# Head.net
KiCad netlist of a schematic drawn in Altium Designer
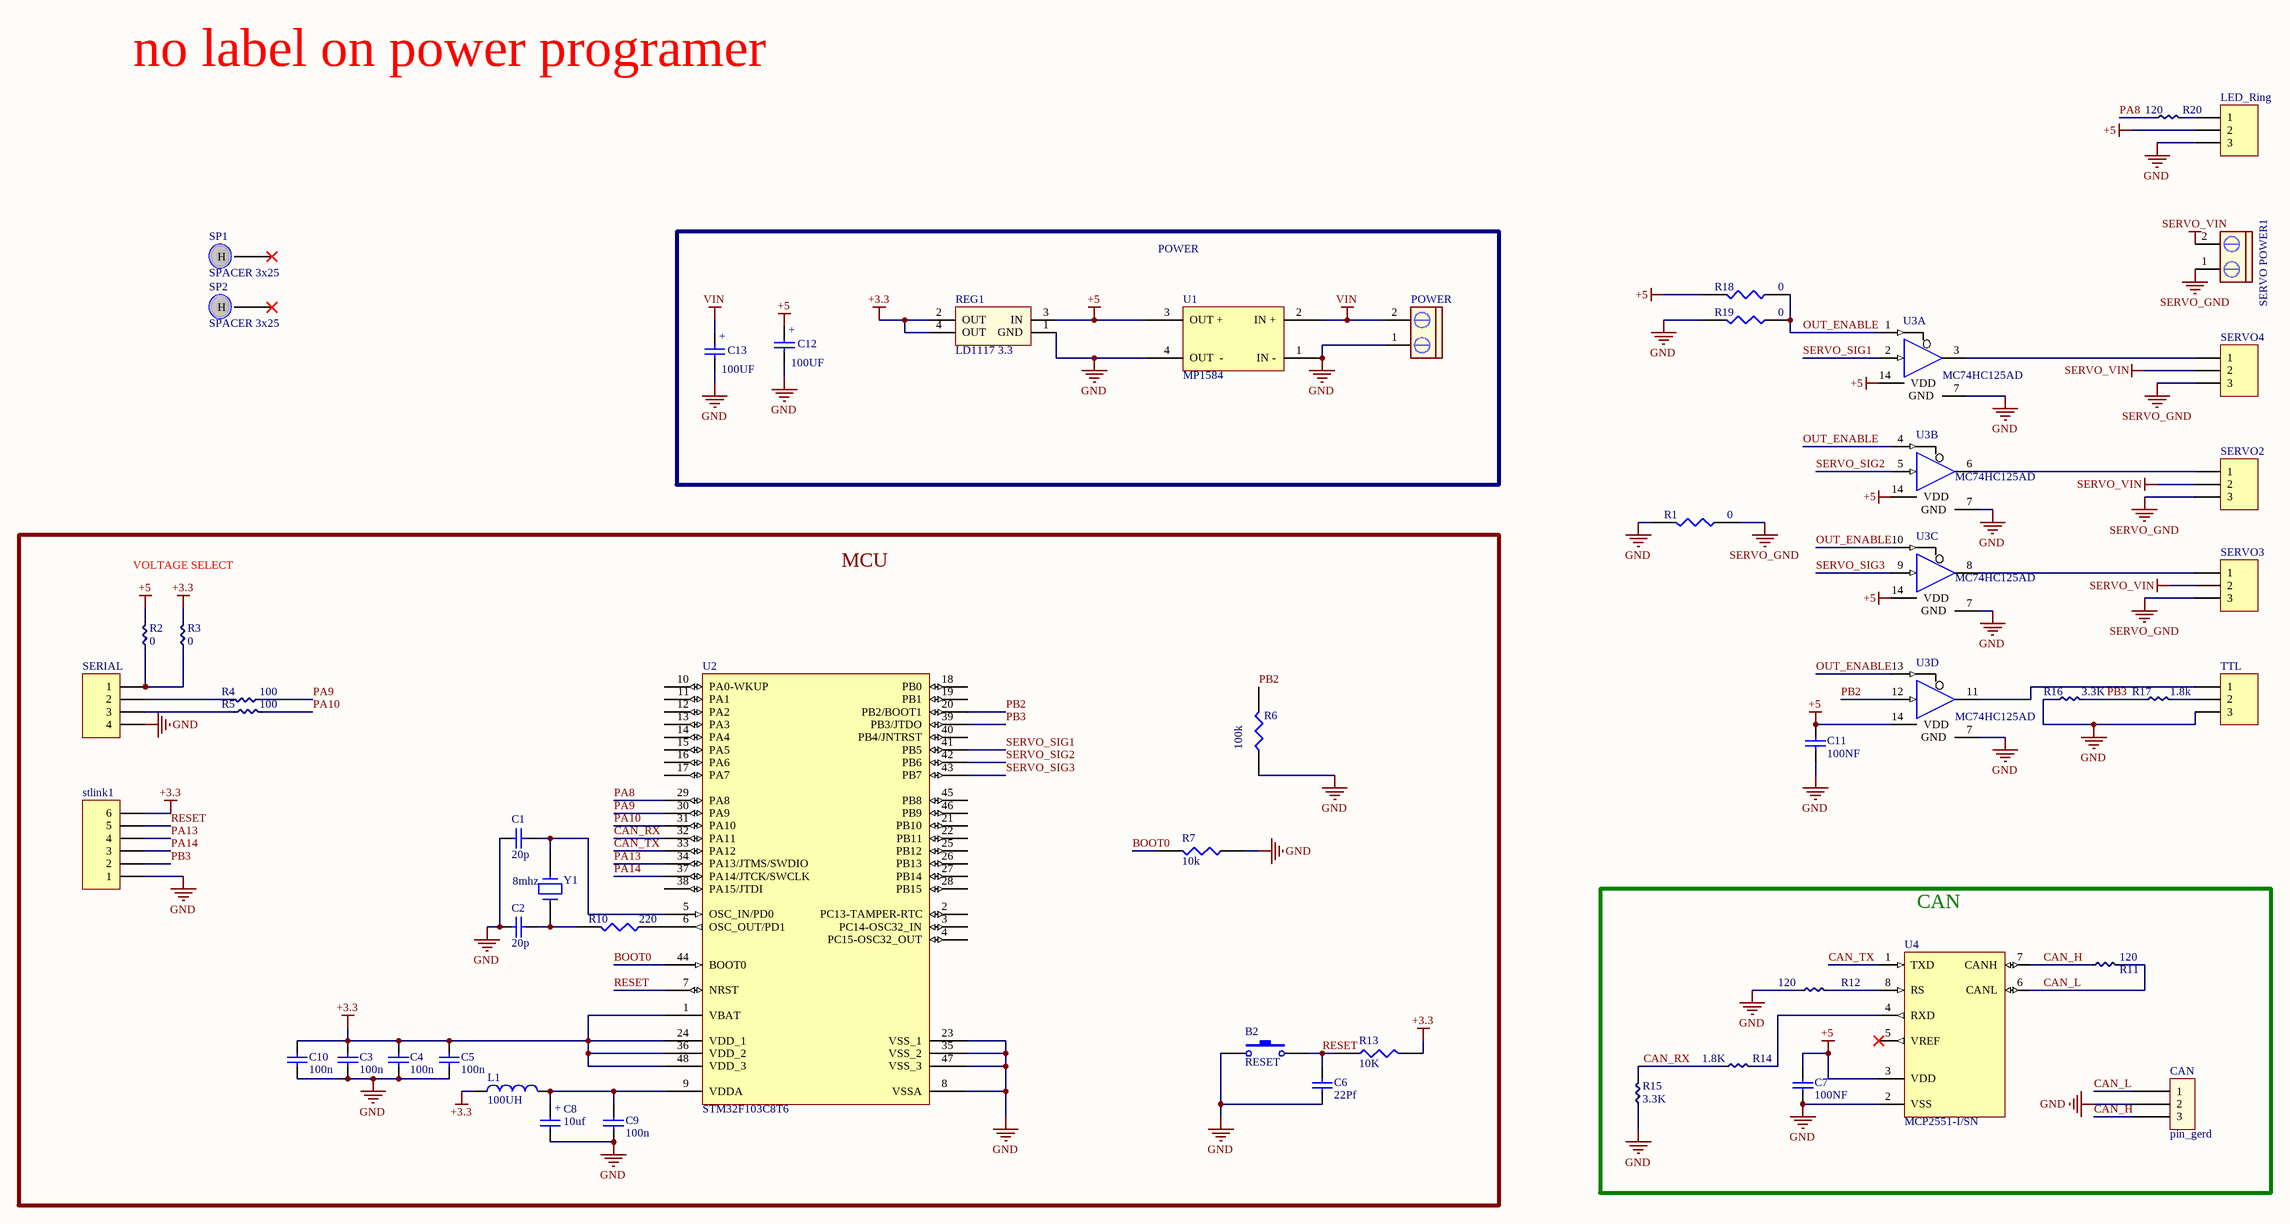
[diagram p0: Head.SchDoc]

(export (version "E")
  (design (tool "Eeschema 10.0.6"))
  (components
    (comp (ref "B2")
      (value "RESET")
      (footprint "SMD PUSH BUTTON")
      (libsource (lib "AMINLIB") (part "SMD_PUSH_BUTTON"))
    )
    (comp (ref "C1") (value "20p") (footprint "MY_CAP_SMD_0805") (libsource (lib "AMINLIB") (part "CAP SMD")))
    (comp (ref "C2") (value "20p") (footprint "MY_CAP_SMD_0805") (libsource (lib "AMINLIB") (part "CAP SMD")))
    (comp (ref "C3")
      (value "100n")
      (footprint "MY_CAP_SMD_0805")
      (libsource (lib "AMINLIB") (part "CAP SMD"))
    )
    (comp (ref "C4")
      (value "100n")
      (footprint "MY_CAP_SMD_0805")
      (libsource (lib "AMINLIB") (part "CAP SMD"))
    )
    (comp (ref "C5")
      (value "100n")
      (footprint "MY_CAP_SMD_0805")
      (libsource (lib "AMINLIB") (part "CAP SMD"))
    )
    (comp (ref "C6")
      (value "22Pf")
      (footprint "MY_CAP_SMD_0805")
      (libsource (lib "AMINLIB") (part "CAP SMD"))
    )
    (comp (ref "C7")
      (value "100NF")
      (footprint "MY_CAP_SMD_0805")
      (description "2.0 mm × 1.25 mm")
      (libsource (lib "AMINLIB") (part "CAP SMD_0805"))
    )
    (comp (ref "C8")
      (value "10uf")
      (footprint "MY_cap_smd10uf")
      (libsource (lib "AMINLIB") (part "cap_smd_10u"))
    )
    (comp (ref "C9")
      (value "100n")
      (footprint "MY_CAP_SMD_0805")
      (libsource (lib "AMINLIB") (part "CAP SMD"))
    )
    (comp (ref "C10")
      (value "100n")
      (footprint "MY_CAP_SMD_0805")
      (libsource (lib "AMINLIB") (part "CAP SMD"))
    )
    (comp (ref "C11")
      (value "100NF")
      (footprint "MY_CAP_SMD_0805")
      (description "2.0 mm × 1.25 mm")
      (libsource (lib "AMINLIB") (part "CAP SMD_0805"))
    )
    (comp (ref "C12")
      (value "100UF")
      (footprint "MY_CAP_POL 5MM")
      (description "CAP-3300Uf")
      (libsource (lib "AMINLIB") (part "Cap Pol_5mm"))
    )
    (comp (ref "C13")
      (value "100UF")
      (footprint "MY_CAP_POL 5MM")
      (description "CAP-3300Uf")
      (libsource (lib "AMINLIB") (part "Cap Pol_5mm"))
    )
    (comp (ref "CAN")
      (value "pin_gerd")
      (footprint "MY_PINGERD3")
      (description "3pin")
      (libsource (lib "AMINLIB") (part "pin_gerd"))
    )
    (comp (ref "L1")
      (value "100UH")
      (footprint "MY_SMD_INDUCTOR")
      (libsource (lib "AMINLIB") (part "INDUCTOR SMD"))
    )
    (comp (ref "LED_Ring")
      (value "Header 3")
      (footprint "My_1X03")
      (description "Header, 3-Pin")
      (fields (field (name "PUBLISHER") "Altium Limited"))
      (libsource (lib "AMINLIB") (part "Header 3"))
    )
    (comp (ref "POWER")
      (value "CON2 pin blue")
      (footprint "My_CN2")
      (description "Connector blue screw")
      (libsource (lib "AMINLIB") (part "CON2 pin blue"))
    )
    (comp (ref "R1") (value "0") (footprint "MY_RES_SMD_0805") (libsource (lib "AMINLIB") (part "RES SMD")))
    (comp (ref "R2")
      (value "0")
      (footprint "MY_RES_SMD_0805")
      (libsource (lib "AMINLIB") (part "RES SMD 0805"))
    )
    (comp (ref "R3")
      (value "0")
      (footprint "MY_RES_SMD_0805")
      (libsource (lib "AMINLIB") (part "RES SMD 0805"))
    )
    (comp (ref "R4")
      (value "100")
      (footprint "MY_RES_SMD_0805")
      (libsource (lib "AMINLIB") (part "RES SMD 0805"))
    )
    (comp (ref "R5")
      (value "100")
      (footprint "MY_RES_SMD_0805")
      (libsource (lib "AMINLIB") (part "RES SMD 0805"))
    )
    (comp (ref "R6")
      (value "100k")
      (footprint "MY_RES_SMD_0805")
      (libsource (lib "AMINLIB") (part "RES SMD"))
    )
    (comp (ref "R7") (value "10k") (footprint "MY_RES_SMD_0805") (libsource (lib "AMINLIB") (part "RES SMD")))
    (comp (ref "R10")
      (value "220")
      (footprint "MY_RES_SMD_0805")
      (libsource (lib "AMINLIB") (part "RES SMD"))
    )
    (comp (ref "R11")
      (value "120")
      (footprint "MY_RES_SMD_0805")
      (libsource (lib "AMINLIB") (part "RES SMD 0805"))
    )
    (comp (ref "R12")
      (value "120")
      (footprint "MY_RES_SMD_0805")
      (libsource (lib "AMINLIB") (part "RES SMD 0805"))
    )
    (comp (ref "R13")
      (value "10K")
      (footprint "MY_RES_SMD_0805")
      (libsource (lib "AMINLIB") (part "RES SMD"))
    )
    (comp (ref "R14")
      (value "1.8K")
      (footprint "MY_RES_SMD_0805")
      (libsource (lib "AMINLIB") (part "RES SMD 0805"))
    )
    (comp (ref "R15")
      (value "3.3K")
      (footprint "MY_RES_SMD_0805")
      (libsource (lib "AMINLIB") (part "RES SMD 0805"))
    )
    (comp (ref "R16")
      (value "3.3K")
      (footprint "MY_RES_SMD_0805")
      (libsource (lib "AMINLIB") (part "RES SMD 0805"))
    )
    (comp (ref "R17")
      (value "1.8k")
      (footprint "MY_RES_SMD_0805")
      (libsource (lib "AMINLIB") (part "RES SMD 0805"))
    )
    (comp (ref "R18") (value "0") (footprint "MY_RES_SMD_0805") (libsource (lib "AMINLIB") (part "RES SMD")))
    (comp (ref "R19") (value "0") (footprint "MY_RES_SMD_0805") (libsource (lib "AMINLIB") (part "RES SMD")))
    (comp (ref "R20")
      (value "120")
      (footprint "MY_RES_SMD_0805")
      (libsource (lib "AMINLIB") (part "RES SMD 0805"))
    )
    (comp (ref "REG1")
      (value "LD1117 3.3")
      (footprint "MY_LD1117-3.3")
      (libsource (lib "AMINLIB") (part "LD1117 3.3"))
    )
    (comp (ref "SERIAL")
      (value "Header 4")
      (footprint "My_1X04")
      (description "Header, 4-Pin")
      (fields (field (name "PUBLISHER") "Altium Limited"))
      (libsource (lib "AMINLIB") (part "Header 4"))
    )
    (comp (ref "SERVO POWER1")
      (value "CON2 pin blue")
      (footprint "My_CN2")
      (description "Connector blue screw")
      (libsource (lib "AMINLIB") (part "CON2 pin blue"))
    )
    (comp (ref "SERVO2")
      (value "Header 3")
      (footprint "My_1X03")
      (description "Header, 3-Pin")
      (fields (field (name "PUBLISHER") "Altium Limited"))
      (libsource (lib "AMINLIB") (part "Header 3"))
    )
    (comp (ref "SERVO3")
      (value "Header 3")
      (footprint "My_1X03")
      (description "Header, 3-Pin")
      (fields (field (name "PUBLISHER") "Altium Limited"))
      (libsource (lib "AMINLIB") (part "Header 3"))
    )
    (comp (ref "SERVO4")
      (value "Header 3")
      (footprint "My_1X03")
      (description "Header, 3-Pin")
      (fields (field (name "PUBLISHER") "Altium Limited"))
      (libsource (lib "AMINLIB") (part "Header 3"))
    )
    (comp (ref "SP1")
      (value "SPACER 3x25")
      (footprint "MY_SPACER 3X25MM")
      (description "SACER 3MM")
      (libsource (lib "AMINLIB") (part "SPACER 3x25"))
    )
    (comp (ref "SP2")
      (value "SPACER 3x25")
      (footprint "MY_SPACER 3X25MM")
      (description "SACER 3MM")
      (libsource (lib "AMINLIB") (part "SPACER 3x25"))
    )
    (comp (ref "stlink1")
      (value "Header 6")
      (footprint "My_1X06")
      (description "Header, 6-Pin")
      (fields (field (name "PUBLISHER") "Altium Limited"))
      (libsource (lib "AMINLIB") (part "Header 6"))
    )
    (comp (ref "TTL")
      (value "Header 3")
      (footprint "My_1X03")
      (description "Header, 3-Pin")
      (fields (field (name "PUBLISHER") "Altium Limited"))
      (libsource (lib "AMINLIB") (part "Header 3"))
    )
    (comp (ref "U1")
      (value "MP1584")
      (footprint "mp1584")
      (description "SWITCHING REGULATOR MODULE")
      (libsource (lib "AMINLIB") (part "MP1584"))
    )
    (comp (ref "U2")
      (value "STM32F103C8T6")
      (footprint "LQFP48_N")
      (description "STM32 ARM-based 32-bit MCU with 64 Kbytes Flash, 48-pin LQFP, Industrial Temperature")
      (fields (field (name "PUBLISHER") "Altium Limited"))
      (libsource (lib "ST Microcontroller 32-Bit STM32") (part "STM32F103C8T6"))
    )
    (comp (ref "U3")
      (value "MC74HC125AD")
      (footprint "751A-02_N")
      (description "Quad 3-State Non-Inverting Buffer")
      (fields (field (name "PUBLISHER") "Altium Limited"))
      (libsource (lib "Motorola Logic Buffer Line Driver") (part "MC74HC125AD"))
    )
    (comp (ref "U4")
      (value "MCP2551-I/SN")
      (footprint "SOIC-SN8_N")
      (description "High-Speed CAN Transceiver, 8-Pin SOIC, Industrial Temperature")
      (fields (field (name "PUBLISHER") "Altium Limited"))
      (libsource (lib "Microchip Interface") (part "MCP2551-I/SN"))
    )
    (comp (ref "Y1")
      (value "8mhz")
      (footprint "My_Crystal - SMD")
      (description "Crystal")
      (libsource (lib "AMINLIB") (part "CRYSTAL"))
    )
  )
  (nets
    (net (code "1") (name "+3.3") (class "Default")
      (node (ref "C10") (pin "2") (pinfunction "2_2") (pintype "passive"))
      (node (ref "C3") (pin "2") (pinfunction "2_2") (pintype "passive"))
      (node (ref "C4") (pin "2") (pinfunction "2_2") (pintype "passive"))
      (node (ref "C5") (pin "2") (pinfunction "2_2") (pintype "passive"))
      (node (ref "L1") (pin "1") (pinfunction "1_1") (pintype "passive"))
      (node (ref "R13") (pin "2") (pinfunction "2_2") (pintype "passive"))
      (node (ref "R3") (pin "2") (pinfunction "2_2") (pintype "passive"))
      (node (ref "REG1") (pin "2") (pinfunction "OUT_2") (pintype "power_in"))
      (node (ref "REG1") (pin "4") (pinfunction "OUT_4") (pintype "power_in"))
      (node (ref "U2") (pin "1") (pinfunction "VBAT_1") (pintype "power_in"))
      (node (ref "U2") (pin "24") (pinfunction "VDD_1_24") (pintype "power_in"))
      (node (ref "U2") (pin "36") (pinfunction "VDD_2_36") (pintype "power_in"))
      (node (ref "U2") (pin "48") (pinfunction "VDD_3_48") (pintype "power_in"))
      (node (ref "stlink1") (pin "6") (pinfunction "6_6") (pintype "passive"))
    )
    (net (code "2") (name "+5") (class "Default")
      (node (ref "C11") (pin "2") (pinfunction "2_2") (pintype "passive"))
      (node (ref "C12") (pin "+") (pinfunction "+_+") (pintype "passive"))
      (node (ref "C7") (pin "2") (pinfunction "2_2") (pintype "passive"))
      (node (ref "LED_Ring") (pin "2") (pinfunction "2_2") (pintype "passive"))
      (node (ref "R18") (pin "2") (pinfunction "2_2") (pintype "passive"))
      (node (ref "R2") (pin "2") (pinfunction "2_2") (pintype "passive"))
      (node (ref "REG1") (pin "3") (pinfunction "IN_3") (pintype "power_in"))
      (node (ref "U1") (pin "3") (pinfunction "OUT_+_3") (pintype "passive"))
      (node (ref "U3") (pin "14") (pinfunction "VDD_14") (pintype "power_in"))
      (node (ref "U4") (pin "3") (pinfunction "VDD_3") (pintype "power_in"))
    )
    (net (code "3") (name "/BOOT0") (class "Default")
      (node (ref "R7") (pin "2") (pinfunction "2_2") (pintype "passive"))
      (node (ref "U2") (pin "44") (pinfunction "BOOT0_44") (pintype "input"))
    )
    (net (code "4") (name "/CAN_H") (class "Default")
      (node (ref "CAN") (pin "3") (pinfunction "3_3") (pintype "passive"))
      (node (ref "R11") (pin "1") (pinfunction "1_1") (pintype "passive"))
      (node (ref "U4") (pin "7") (pinfunction "CANH_7") (pintype "bidirectional"))
    )
    (net (code "5") (name "/CAN_L") (class "Default")
      (node (ref "CAN") (pin "1") (pinfunction "1_1") (pintype "passive"))
      (node (ref "R11") (pin "2") (pinfunction "2_2") (pintype "passive"))
      (node (ref "U4") (pin "6") (pinfunction "CANL_6") (pintype "bidirectional"))
    )
    (net (code "6") (name "/CAN_RX") (class "Default")
      (node (ref "R14") (pin "1") (pinfunction "1_1") (pintype "passive"))
      (node (ref "R15") (pin "2") (pinfunction "2_2") (pintype "passive"))
      (node (ref "U2") (pin "32") (pinfunction "PA11_32") (pintype "bidirectional"))
    )
    (net (code "7") (name "/CAN_TX") (class "Default")
      (node (ref "U2") (pin "33") (pinfunction "PA12_33") (pintype "bidirectional"))
      (node (ref "U4") (pin "1") (pinfunction "TXD_1") (pintype "input"))
    )
    (net (code "8") (name "/OUT_ENABLE") (class "Default")
      (node (ref "R18") (pin "1") (pinfunction "1_1") (pintype "passive"))
      (node (ref "R19") (pin "1") (pinfunction "1_1") (pintype "passive"))
      (node (ref "U3") (pin "1") (pinfunction "~{OE}_1") (pintype "input"))
      (node (ref "U3") (pin "10") (pinfunction "~{OE}_10") (pintype "input"))
      (node (ref "U3") (pin "13") (pinfunction "~{OE}_13") (pintype "input"))
      (node (ref "U3") (pin "4") (pinfunction "~{OE}_4") (pintype "input"))
    )
    (net (code "9") (name "/PA8") (class "Default")
      (node (ref "R20") (pin "1") (pinfunction "1_1") (pintype "passive"))
      (node (ref "U2") (pin "29") (pinfunction "PA8_29") (pintype "bidirectional"))
    )
    (net (code "10") (name "/PA9") (class "Default")
      (node (ref "R4") (pin "1") (pinfunction "1_1") (pintype "passive"))
      (node (ref "U2") (pin "30") (pinfunction "PA9_30") (pintype "bidirectional"))
    )
    (net (code "11") (name "/PA10") (class "Default")
      (node (ref "R5") (pin "2") (pinfunction "2_2") (pintype "passive"))
      (node (ref "U2") (pin "31") (pinfunction "PA10_31") (pintype "bidirectional"))
    )
    (net (code "12") (name "/PA13") (class "Default")
      (node (ref "U2") (pin "34") (pinfunction "PA13/JTMS/SWDIO_34") (pintype "bidirectional"))
      (node (ref "stlink1") (pin "4") (pinfunction "4_4") (pintype "passive"))
    )
    (net (code "13") (name "/PA14") (class "Default")
      (node (ref "U2") (pin "37") (pinfunction "PA14/JTCK/SWCLK_37") (pintype "bidirectional"))
      (node (ref "stlink1") (pin "3") (pinfunction "3_3") (pintype "passive"))
    )
    (net (code "14") (name "/PB2") (class "Default")
      (node (ref "R6") (pin "2") (pinfunction "2_2") (pintype "passive"))
      (node (ref "U2") (pin "20") (pinfunction "PB2/BOOT1_20") (pintype "bidirectional"))
      (node (ref "U3") (pin "12") (pinfunction "A_12") (pintype "input"))
    )
    (net (code "15") (name "/PB3") (class "Default")
      (node (ref "R16") (pin "2") (pinfunction "2_2") (pintype "passive"))
      (node (ref "R17") (pin "1") (pinfunction "1_1") (pintype "passive"))
      (node (ref "U2") (pin "39") (pinfunction "PB3/JTDO_39") (pintype "bidirectional"))
      (node (ref "stlink1") (pin "2") (pinfunction "2_2") (pintype "passive"))
    )
    (net (code "16") (name "/RESET") (class "Default")
      (node (ref "B2") (pin "2") (pinfunction "2_2") (pintype "passive"))
      (node (ref "C6") (pin "2") (pinfunction "2_2") (pintype "passive"))
      (node (ref "R13") (pin "1") (pinfunction "1_1") (pintype "passive"))
      (node (ref "U2") (pin "7") (pinfunction "NRST_7") (pintype "bidirectional"))
      (node (ref "stlink1") (pin "5") (pinfunction "5_5") (pintype "passive"))
    )
    (net (code "17") (name "/SERVO_SIG1") (class "Default")
      (node (ref "U2") (pin "41") (pinfunction "PB5_41") (pintype "bidirectional"))
      (node (ref "U3") (pin "2") (pinfunction "A_2") (pintype "input"))
    )
    (net (code "18") (name "/SERVO_SIG2") (class "Default")
      (node (ref "U2") (pin "42") (pinfunction "PB6_42") (pintype "bidirectional"))
      (node (ref "U3") (pin "5") (pinfunction "A_5") (pintype "input"))
    )
    (net (code "19") (name "/SERVO_SIG3") (class "Default")
      (node (ref "U2") (pin "43") (pinfunction "PB7_43") (pintype "bidirectional"))
      (node (ref "U3") (pin "9") (pinfunction "A_9") (pintype "input"))
    )
    (net (code "20") (name "GND") (class "Default")
      (node (ref "B2") (pin "1") (pinfunction "1_1") (pintype "passive"))
      (node (ref "C1") (pin "2") (pinfunction "2_2") (pintype "passive"))
      (node (ref "C10") (pin "1") (pinfunction "1_1") (pintype "passive"))
      (node (ref "C11") (pin "1") (pinfunction "1_1") (pintype "passive"))
      (node (ref "C12") (pin "-") (pinfunction "-_-") (pintype "passive"))
      (node (ref "C13") (pin "-") (pinfunction "-_-") (pintype "passive"))
      (node (ref "C2") (pin "1") (pinfunction "1_1") (pintype "passive"))
      (node (ref "C3") (pin "1") (pinfunction "1_1") (pintype "passive"))
      (node (ref "C4") (pin "1") (pinfunction "1_1") (pintype "passive"))
      (node (ref "C5") (pin "1") (pinfunction "1_1") (pintype "passive"))
      (node (ref "C6") (pin "1") (pinfunction "1_1") (pintype "passive"))
      (node (ref "C7") (pin "1") (pinfunction "1_1") (pintype "passive"))
      (node (ref "C8") (pin "-") (pinfunction "-_-") (pintype "passive"))
      (node (ref "C9") (pin "1") (pinfunction "1_1") (pintype "passive"))
      (node (ref "CAN") (pin "2") (pinfunction "2_2") (pintype "passive"))
      (node (ref "LED_Ring") (pin "3") (pinfunction "3_3") (pintype "passive"))
      (node (ref "POWER") (pin "1") (pinfunction "1_1") (pintype "passive"))
      (node (ref "R1") (pin "2") (pinfunction "2_2") (pintype "passive"))
      (node (ref "R12") (pin "1") (pinfunction "1_1") (pintype "passive"))
      (node (ref "R15") (pin "1") (pinfunction "1_1") (pintype "passive"))
      (node (ref "R16") (pin "1") (pinfunction "1_1") (pintype "passive"))
      (node (ref "R19") (pin "2") (pinfunction "2_2") (pintype "passive"))
      (node (ref "R6") (pin "1") (pinfunction "1_1") (pintype "passive"))
      (node (ref "R7") (pin "1") (pinfunction "1_1") (pintype "passive"))
      (node (ref "REG1") (pin "1") (pinfunction "GND_1") (pintype "power_in"))
      (node (ref "SERIAL") (pin "4") (pinfunction "4_4") (pintype "passive"))
      (node (ref "TTL") (pin "3") (pinfunction "3_3") (pintype "passive"))
      (node (ref "U1") (pin "1") (pinfunction "IN_-_1") (pintype "passive"))
      (node (ref "U1") (pin "4") (pinfunction "OUT__-_4") (pintype "passive"))
      (node (ref "U2") (pin "23") (pinfunction "VSS_1_23") (pintype "power_in"))
      (node (ref "U2") (pin "35") (pinfunction "VSS_2_35") (pintype "power_in"))
      (node (ref "U2") (pin "47") (pinfunction "VSS_3_47") (pintype "power_in"))
      (node (ref "U2") (pin "8") (pinfunction "VSSA_8") (pintype "power_in"))
      (node (ref "U3") (pin "7") (pinfunction "GND_7") (pintype "power_in"))
      (node (ref "U4") (pin "2") (pinfunction "VSS_2") (pintype "power_in"))
      (node (ref "stlink1") (pin "1") (pinfunction "1_1") (pintype "passive"))
    )
    (net (code "21") (name "Net-(C2-Pad2)") (class "Default")
      (node (ref "C2") (pin "2") (pinfunction "2_2") (pintype "passive"))
      (node (ref "R10") (pin "2") (pinfunction "2_2") (pintype "passive"))
      (node (ref "Y1") (pin "1") (pinfunction "1_1") (pintype "passive"))
    )
    (net (code "22") (name "Net-(LED_Ring-Pad1)") (class "Default")
      (node (ref "LED_Ring") (pin "1") (pinfunction "1_1") (pintype "passive"))
      (node (ref "R20") (pin "2") (pinfunction "2_2") (pintype "passive"))
    )
    (net (code "23") (name "Net-(R2-Pad1)") (class "Default")
      (node (ref "R2") (pin "1") (pinfunction "1_1") (pintype "passive"))
      (node (ref "R3") (pin "1") (pinfunction "1_1") (pintype "passive"))
      (node (ref "SERIAL") (pin "1") (pinfunction "1_1") (pintype "passive"))
    )
    (net (code "24") (name "Net-(R4-Pad2)") (class "Default")
      (node (ref "R4") (pin "2") (pinfunction "2_2") (pintype "passive"))
      (node (ref "SERIAL") (pin "2") (pinfunction "2_2") (pintype "passive"))
    )
    (net (code "25") (name "Net-(R5-Pad1)") (class "Default")
      (node (ref "R5") (pin "1") (pinfunction "1_1") (pintype "passive"))
      (node (ref "SERIAL") (pin "3") (pinfunction "3_3") (pintype "passive"))
    )
    (net (code "26") (name "Net-(R17-Pad2)") (class "Default")
      (node (ref "R17") (pin "2") (pinfunction "2_2") (pintype "passive"))
      (node (ref "TTL") (pin "2") (pinfunction "2_2") (pintype "passive"))
    )
    (net (code "27") (name "Net-(U2-OSC_IN{slash}PD0)") (class "Default")
      (node (ref "C1") (pin "1") (pinfunction "1_1") (pintype "passive"))
      (node (ref "U2") (pin "5") (pinfunction "OSC_IN/PD0_5") (pintype "input"))
      (node (ref "Y1") (pin "2") (pinfunction "2_2") (pintype "passive"))
    )
    (net (code "28") (name "Net-(U2-OSC_OUT{slash}PD1)") (class "Default")
      (node (ref "R10") (pin "1") (pinfunction "1_1") (pintype "passive"))
      (node (ref "U2") (pin "6") (pinfunction "OSC_OUT/PD1_6") (pintype "output"))
    )
    (net (code "29") (name "Net-(U2-VDDA)") (class "Default")
      (node (ref "C8") (pin "+") (pinfunction "+_+") (pintype "passive"))
      (node (ref "C9") (pin "2") (pinfunction "2_2") (pintype "passive"))
      (node (ref "L1") (pin "2") (pinfunction "2_2") (pintype "passive"))
      (node (ref "U2") (pin "9") (pinfunction "VDDA_9") (pintype "power_in"))
    )
    (net (code "30") (name "Net-(U3A-Y)") (class "Default")
      (node (ref "SERVO4") (pin "1") (pinfunction "1_1") (pintype "passive"))
      (node (ref "U3") (pin "3") (pinfunction "Y_3") (pintype "tri_state"))
    )
    (net (code "31") (name "Net-(U3B-Y)") (class "Default")
      (node (ref "SERVO2") (pin "1") (pinfunction "1_1") (pintype "passive"))
      (node (ref "U3") (pin "6") (pinfunction "Y_6") (pintype "tri_state"))
    )
    (net (code "32") (name "Net-(U3C-Y)") (class "Default")
      (node (ref "SERVO3") (pin "1") (pinfunction "1_1") (pintype "passive"))
      (node (ref "U3") (pin "8") (pinfunction "Y_8") (pintype "tri_state"))
    )
    (net (code "33") (name "Net-(U3D-Y)") (class "Default")
      (node (ref "TTL") (pin "1") (pinfunction "1_1") (pintype "passive"))
      (node (ref "U3") (pin "11") (pinfunction "Y_11") (pintype "tri_state"))
    )
    (net (code "34") (name "Net-(U4-RS)") (class "Default")
      (node (ref "R12") (pin "2") (pinfunction "2_2") (pintype "passive"))
      (node (ref "U4") (pin "8") (pinfunction "RS_8") (pintype "input"))
    )
    (net (code "35") (name "Net-(U4-RXD)") (class "Default")
      (node (ref "R14") (pin "2") (pinfunction "2_2") (pintype "passive"))
      (node (ref "U4") (pin "4") (pinfunction "RXD_4") (pintype "output"))
    )
    (net (code "36") (name "SERVO_GND") (class "Default")
      (node (ref "R1") (pin "1") (pinfunction "1_1") (pintype "passive"))
      (node (ref "SERVO POWER1") (pin "1") (pinfunction "1_1") (pintype "passive"))
      (node (ref "SERVO2") (pin "3") (pinfunction "3_3") (pintype "passive"))
      (node (ref "SERVO3") (pin "3") (pinfunction "3_3") (pintype "passive"))
      (node (ref "SERVO4") (pin "3") (pinfunction "3_3") (pintype "passive"))
    )
    (net (code "37") (name "SERVO_VIN") (class "Default")
      (node (ref "SERVO POWER1") (pin "2") (pinfunction "2_2") (pintype "passive"))
      (node (ref "SERVO2") (pin "2") (pinfunction "2_2") (pintype "passive"))
      (node (ref "SERVO3") (pin "2") (pinfunction "2_2") (pintype "passive"))
      (node (ref "SERVO4") (pin "2") (pinfunction "2_2") (pintype "passive"))
    )
    (net (code "38") (name "VIN") (class "Default")
      (node (ref "C13") (pin "+") (pinfunction "+_+") (pintype "passive"))
      (node (ref "POWER") (pin "2") (pinfunction "2_2") (pintype "passive"))
      (node (ref "U1") (pin "2") (pinfunction "IN_+_2") (pintype "passive"))
    )
    (net (code "39") (name "unconnected-(SP1-H-Pad0)") (class "Default")
      (node (ref "SP1") (pin "0") (pinfunction "H_0") (pintype "passive+no_connect"))
    )
    (net (code "40") (name "unconnected-(SP2-H-Pad0)") (class "Default")
      (node (ref "SP2") (pin "0") (pinfunction "H_0") (pintype "passive+no_connect"))
    )
    (net (code "41") (name "unconnected-(U2-PA0-WKUP-Pad10)") (class "Default")
      (node (ref "U2") (pin "10") (pinfunction "PA0-WKUP_10") (pintype "bidirectional"))
    )
    (net (code "42") (name "unconnected-(U2-PA1-Pad11)") (class "Default")
      (node (ref "U2") (pin "11") (pinfunction "PA1_11") (pintype "bidirectional"))
    )
    (net (code "43") (name "unconnected-(U2-PA2-Pad12)") (class "Default")
      (node (ref "U2") (pin "12") (pinfunction "PA2_12") (pintype "bidirectional"))
    )
    (net (code "44") (name "unconnected-(U2-PA3-Pad13)") (class "Default")
      (node (ref "U2") (pin "13") (pinfunction "PA3_13") (pintype "bidirectional"))
    )
    (net (code "45") (name "unconnected-(U2-PA4-Pad14)") (class "Default")
      (node (ref "U2") (pin "14") (pinfunction "PA4_14") (pintype "bidirectional"))
    )
    (net (code "46") (name "unconnected-(U2-PA5-Pad15)") (class "Default")
      (node (ref "U2") (pin "15") (pinfunction "PA5_15") (pintype "bidirectional"))
    )
    (net (code "47") (name "unconnected-(U2-PA6-Pad16)") (class "Default")
      (node (ref "U2") (pin "16") (pinfunction "PA6_16") (pintype "bidirectional"))
    )
    (net (code "48") (name "unconnected-(U2-PA7-Pad17)") (class "Default")
      (node (ref "U2") (pin "17") (pinfunction "PA7_17") (pintype "bidirectional"))
    )
    (net (code "49") (name "unconnected-(U2-PA15{slash}JTDI-Pad38)") (class "Default")
      (node (ref "U2") (pin "38") (pinfunction "PA15/JTDI_38") (pintype "bidirectional"))
    )
    (net (code "50") (name "unconnected-(U2-PB0-Pad18)") (class "Default")
      (node (ref "U2") (pin "18") (pinfunction "PB0_18") (pintype "bidirectional"))
    )
    (net (code "51") (name "unconnected-(U2-PB1-Pad19)") (class "Default")
      (node (ref "U2") (pin "19") (pinfunction "PB1_19") (pintype "bidirectional"))
    )
    (net (code "52") (name "unconnected-(U2-PB4{slash}JNTRST-Pad40)") (class "Default")
      (node (ref "U2") (pin "40") (pinfunction "PB4/JNTRST_40") (pintype "bidirectional"))
    )
    (net (code "53") (name "unconnected-(U2-PB8-Pad45)") (class "Default")
      (node (ref "U2") (pin "45") (pinfunction "PB8_45") (pintype "bidirectional"))
    )
    (net (code "54") (name "unconnected-(U2-PB9-Pad46)") (class "Default")
      (node (ref "U2") (pin "46") (pinfunction "PB9_46") (pintype "bidirectional"))
    )
    (net (code "55") (name "unconnected-(U2-PB10-Pad21)") (class "Default")
      (node (ref "U2") (pin "21") (pinfunction "PB10_21") (pintype "bidirectional"))
    )
    (net (code "56") (name "unconnected-(U2-PB11-Pad22)") (class "Default")
      (node (ref "U2") (pin "22") (pinfunction "PB11_22") (pintype "bidirectional"))
    )
    (net (code "57") (name "unconnected-(U2-PB12-Pad25)") (class "Default")
      (node (ref "U2") (pin "25") (pinfunction "PB12_25") (pintype "bidirectional"))
    )
    (net (code "58") (name "unconnected-(U2-PB13-Pad26)") (class "Default")
      (node (ref "U2") (pin "26") (pinfunction "PB13_26") (pintype "bidirectional"))
    )
    (net (code "59") (name "unconnected-(U2-PB14-Pad27)") (class "Default")
      (node (ref "U2") (pin "27") (pinfunction "PB14_27") (pintype "bidirectional"))
    )
    (net (code "60") (name "unconnected-(U2-PB15-Pad28)") (class "Default")
      (node (ref "U2") (pin "28") (pinfunction "PB15_28") (pintype "bidirectional"))
    )
    (net (code "61") (name "unconnected-(U2-PC13-TAMPER-RTC-Pad2)") (class "Default")
      (node (ref "U2") (pin "2") (pinfunction "PC13-TAMPER-RTC_2") (pintype "bidirectional"))
    )
    (net (code "62") (name "unconnected-(U2-PC14-OSC32_IN-Pad3)") (class "Default")
      (node (ref "U2") (pin "3") (pinfunction "PC14-OSC32_IN_3") (pintype "bidirectional"))
    )
    (net (code "63") (name "unconnected-(U2-PC15-OSC32_OUT-Pad4)") (class "Default")
      (node (ref "U2") (pin "4") (pinfunction "PC15-OSC32_OUT_4") (pintype "bidirectional"))
    )
    (net (code "64") (name "unconnected-(U4-VREF-Pad5)") (class "Default")
      (node (ref "U4") (pin "5") (pinfunction "VREF_5") (pintype "output+no_connect"))
    )
  )
)
